# MDBU003_Schematic.net
KiCad netlist of a schematic drawn in Altium Designer
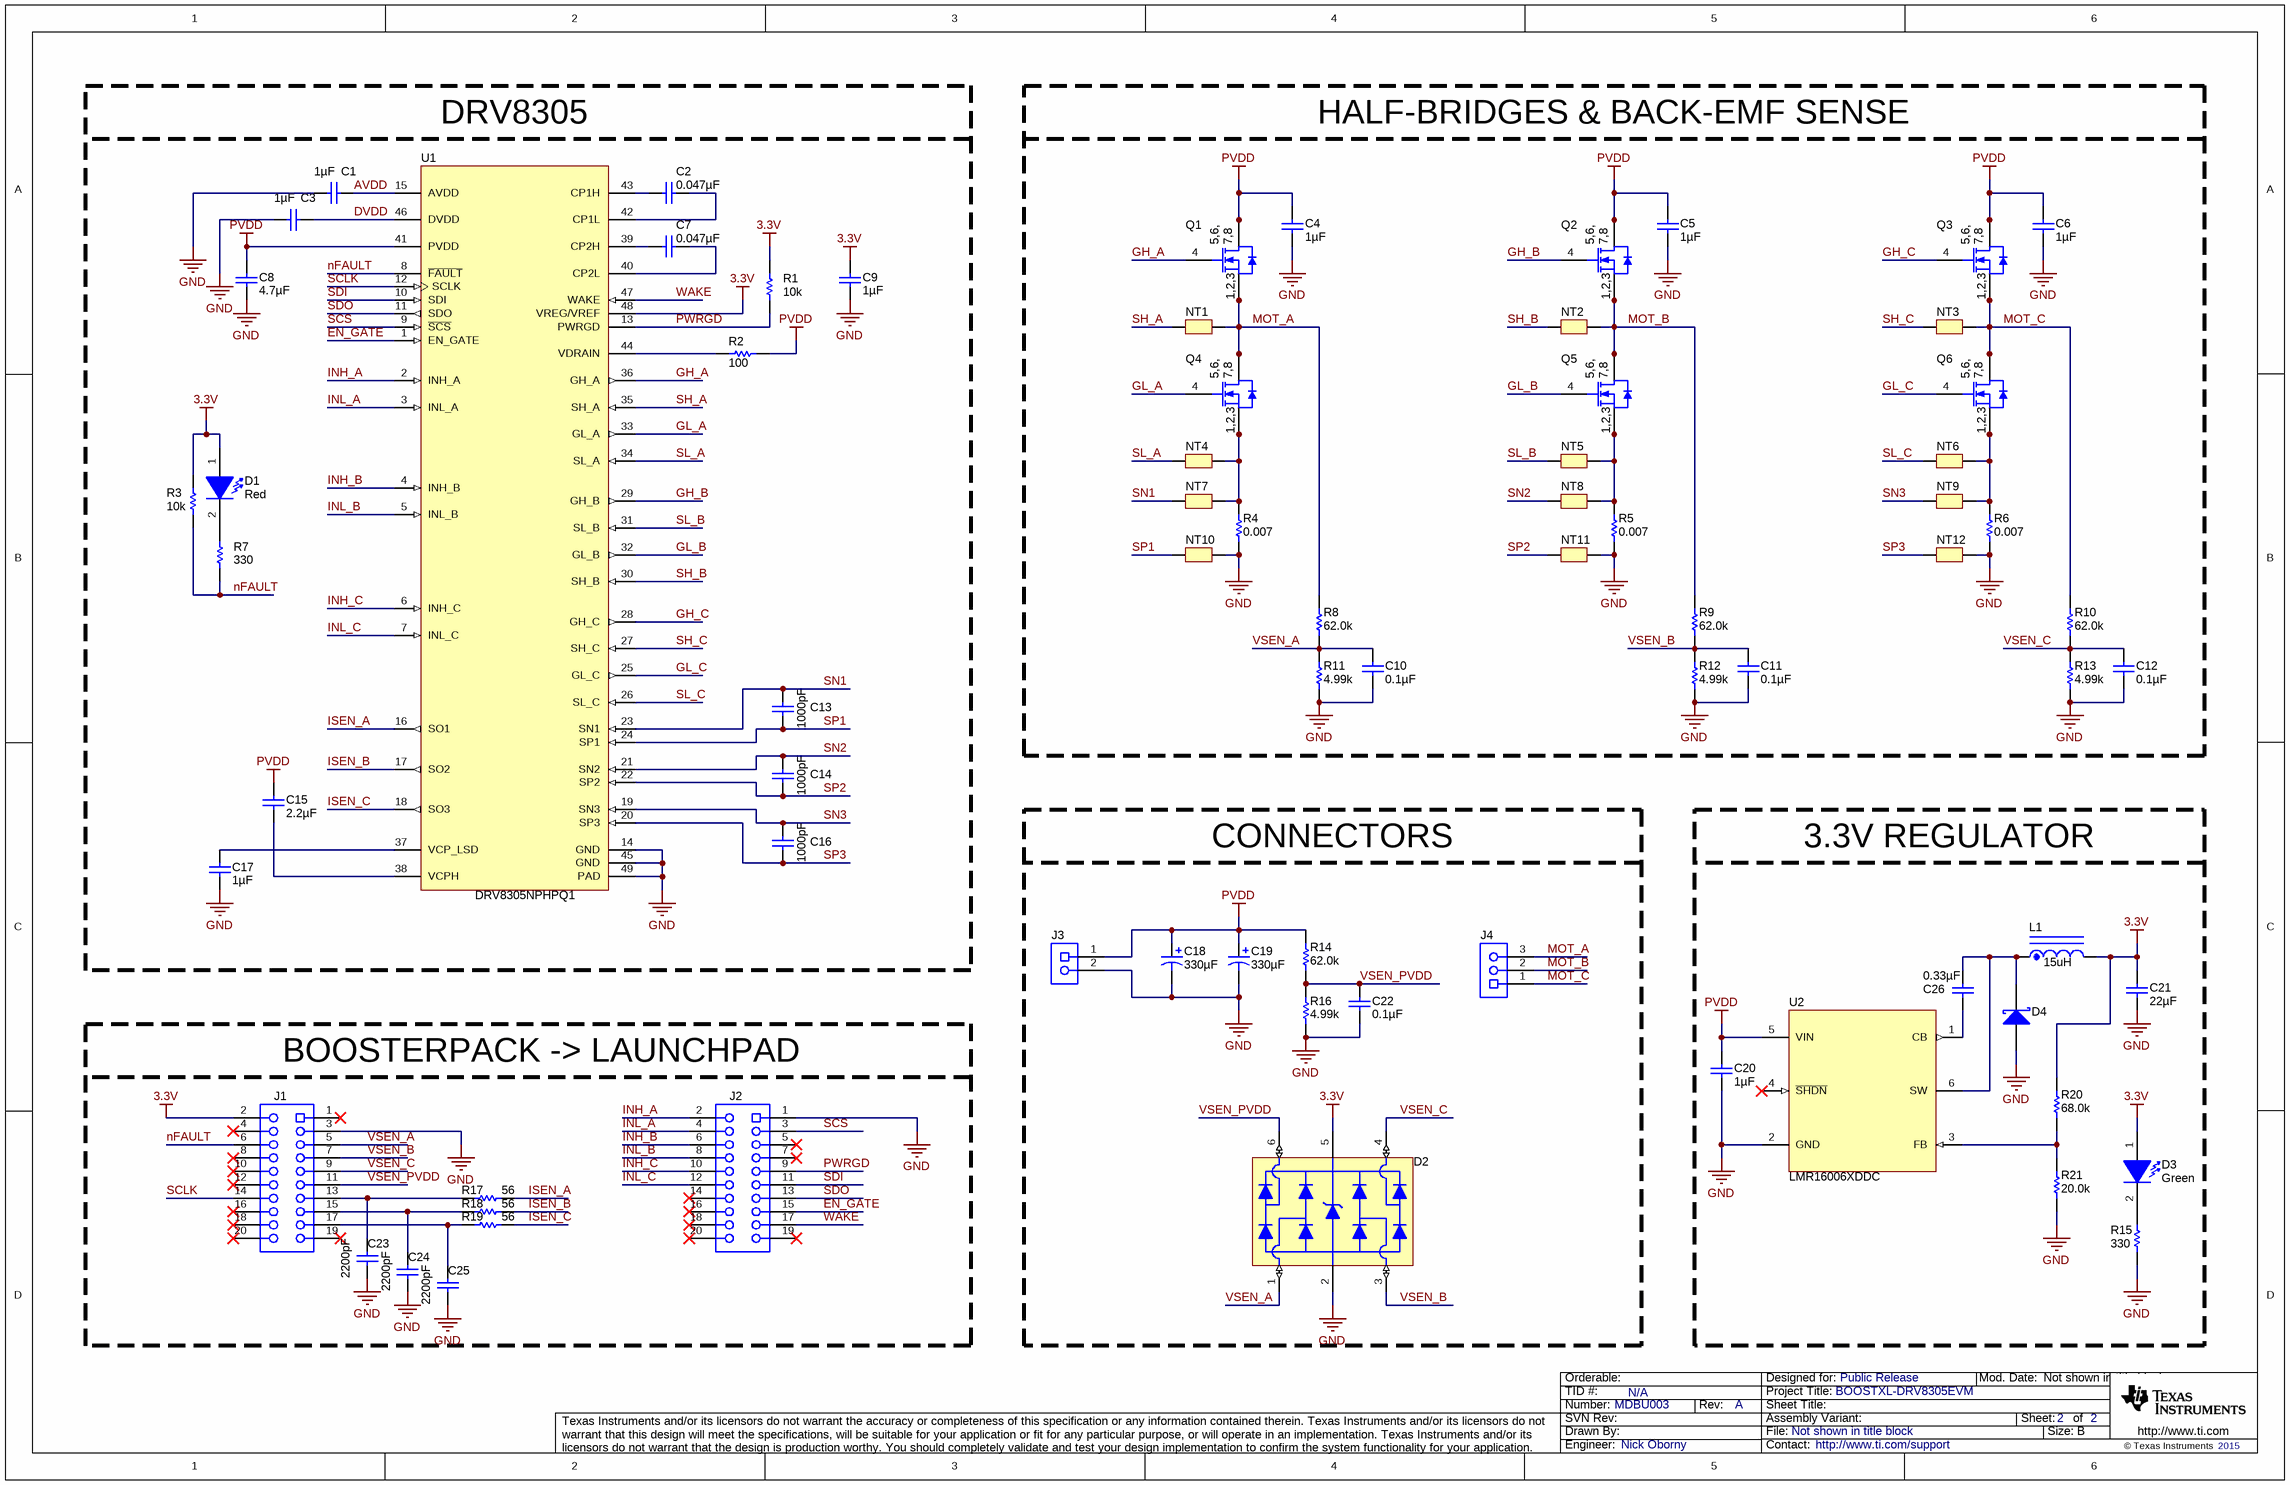
[diagram p0: MDBU003_Schematic.SchDoc]

(export (version "E")
  (design (tool "Eeschema 10.0.6"))
  (components
    (comp (ref "C1")
      (value "C1608X7R1C105K")
      (footprint "0603L")
      (description "CAP, CERM, 1 µF, 16 V, +/- 10%, X7R, 0603")
      (fields
        (field (name "VALUEDISPLAYED") "1µF")
        (field (name "MANUFACTURER") "TDK")
        (field (name "PUBLISHER") "Texas Instruments")
      )
      (libsource (lib "Capacitor_Ceramic") (part "C1608X7R1C105K"))
    )
    (comp (ref "C2")
      (value "C0603C473K1RACTU")
      (footprint "0603L")
      (description "CAP, CERM, 0.047uF, 100V, +/-10%, X7R, 0603")
      (fields
        (field (name "VALUEDISPLAYED") "0.047µF")
        (field (name "MANUFACTURER") "Kemet")
        (field (name "PUBLISHER") "Texas Instruments")
      )
      (libsource (lib "Capacitor_Ceramic") (part "GRM188R72A104KA35D"))
    )
    (comp (ref "C3")
      (value "C1608X7R1C105K")
      (footprint "0603L")
      (description "CAP, CERM, 1 µF, 16 V, +/- 10%, X7R, 0603")
      (fields
        (field (name "VALUEDISPLAYED") "1µF")
        (field (name "MANUFACTURER") "TDK")
        (field (name "PUBLISHER") "Texas Instruments")
      )
      (libsource (lib "Capacitor_Ceramic") (part "C1608X7R1C105K"))
    )
    (comp (ref "C4")
      (value "UMK107AB7105KA-T")
      (footprint "0603L")
      (description "CAP, CERM, 1 µF, 50 V, +/- 10%, X7R, 0603")
      (fields
        (field (name "VALUEDISPLAYED") "1µF")
        (field (name "MANUFACTURER") "Taiyo Yuden")
        (field (name "PUBLISHER") "Texas Instruments")
      )
      (libsource (lib "Capacitor_Ceramic") (part "UMK107AB7105KA-T"))
    )
    (comp (ref "C5")
      (value "UMK107AB7105KA-T")
      (footprint "0603L")
      (description "CAP, CERM, 1 µF, 50 V, +/- 10%, X7R, 0603")
      (fields
        (field (name "VALUEDISPLAYED") "1µF")
        (field (name "MANUFACTURER") "Taiyo Yuden")
        (field (name "PUBLISHER") "Texas Instruments")
      )
      (libsource (lib "Capacitor_Ceramic") (part "UMK107AB7105KA-T"))
    )
    (comp (ref "C6")
      (value "UMK107AB7105KA-T")
      (footprint "0603L")
      (description "CAP, CERM, 1 µF, 50 V, +/- 10%, X7R, 0603")
      (fields
        (field (name "VALUEDISPLAYED") "1µF")
        (field (name "MANUFACTURER") "Taiyo Yuden")
        (field (name "PUBLISHER") "Texas Instruments")
      )
      (libsource (lib "Capacitor_Ceramic") (part "UMK107AB7105KA-T"))
    )
    (comp (ref "C7")
      (value "C0603C473K1RACTU")
      (footprint "0603L")
      (description "CAP, CERM, 0.047uF, 100V, +/-10%, X7R, 0603")
      (fields
        (field (name "VALUEDISPLAYED") "0.047µF")
        (field (name "MANUFACTURER") "Kemet")
        (field (name "PUBLISHER") "Texas Instruments")
      )
      (libsource (lib "Capacitor_Ceramic") (part "GRM188R72A104KA35D"))
    )
    (comp (ref "C8")
      (value "GRM31CR71H475KA12L")
      (footprint "1206L")
      (description "CAP, CERM, 4.7 µF, 50 V, +/- 10%, X7R, 1206")
      (fields
        (field (name "VALUEDISPLAYED") "4.7µF")
        (field (name "MANUFACTURER") "MuRata")
        (field (name "PUBLISHER") "Texas Instruments")
      )
      (libsource (lib "Capacitor_Ceramic") (part "GRM31CR71H475KA12L"))
    )
    (comp (ref "C9")
      (value "C1608X7R1C105K")
      (footprint "0603L")
      (description "CAP, CERM, 1 µF, 16 V, +/- 10%, X7R, 0603")
      (fields
        (field (name "VALUEDISPLAYED") "1µF")
        (field (name "MANUFACTURER") "TDK")
        (field (name "PUBLISHER") "Texas Instruments")
      )
      (libsource (lib "Capacitor_Ceramic") (part "C1608X7R1C105K"))
    )
    (comp (ref "C10")
      (value "C0603C104J4RACTU")
      (footprint "0603L")
      (description "CAP, CERM, 0.1 µF, 16 V, +/- 5%, X7R, 0603")
      (fields
        (field (name "VALUEDISPLAYED") "0.1µF")
        (field (name "MANUFACTURER") "Kemet")
        (field (name "PUBLISHER") "Texas Instruments")
      )
      (libsource (lib "Capacitor_Ceramic") (part "C0603C104J4RACTU"))
    )
    (comp (ref "C11")
      (value "C0603C104J4RACTU")
      (footprint "0603L")
      (description "CAP, CERM, 0.1 µF, 16 V, +/- 5%, X7R, 0603")
      (fields
        (field (name "VALUEDISPLAYED") "0.1µF")
        (field (name "MANUFACTURER") "Kemet")
        (field (name "PUBLISHER") "Texas Instruments")
      )
      (libsource (lib "Capacitor_Ceramic") (part "C0603C104J4RACTU"))
    )
    (comp (ref "C12")
      (value "C0603C104J4RACTU")
      (footprint "0603L")
      (description "CAP, CERM, 0.1 µF, 16 V, +/- 5%, X7R, 0603")
      (fields
        (field (name "VALUEDISPLAYED") "0.1µF")
        (field (name "MANUFACTURER") "Kemet")
        (field (name "PUBLISHER") "Texas Instruments")
      )
      (libsource (lib "Capacitor_Ceramic") (part "C0603C104J4RACTU"))
    )
    (comp (ref "C13")
      (value "GRM188R71C102KA01D")
      (footprint "0603L")
      (description "CAP, CERM, 1000pF, 16V, +/-10%, X7R, 0603")
      (fields
        (field (name "VALUEDISPLAYED") "1000pF")
        (field (name "MANUFACTURER") "MuRata")
        (field (name "PUBLISHER") "Texas Instruments")
      )
      (libsource (lib "Capacitor_Ceramic") (part "GRM188R71C102KA01D"))
    )
    (comp (ref "C14")
      (value "GRM188R71C102KA01D")
      (footprint "0603L")
      (description "CAP, CERM, 1000pF, 16V, +/-10%, X7R, 0603")
      (fields
        (field (name "VALUEDISPLAYED") "1000pF")
        (field (name "MANUFACTURER") "MuRata")
        (field (name "PUBLISHER") "Texas Instruments")
      )
      (libsource (lib "Capacitor_Ceramic") (part "GRM188R71C102KA01D"))
    )
    (comp (ref "C15")
      (value "GRM32ER72A225KA35L")
      (footprint "1210L")
      (description "CAP, CERM, 2.2 µF, 100 V, +/- 10%, X7R, 1210")
      (fields
        (field (name "VALUEDISPLAYED") "2.2µF")
        (field (name "MANUFACTURER") "MuRata")
        (field (name "PUBLISHER") "Texas Instruments")
      )
      (libsource (lib "Capacitor_Ceramic") (part "GRM32ER72A225KA35L"))
    )
    (comp (ref "C16")
      (value "GRM188R71C102KA01D")
      (footprint "0603L")
      (description "CAP, CERM, 1000pF, 16V, +/-10%, X7R, 0603")
      (fields
        (field (name "VALUEDISPLAYED") "1000pF")
        (field (name "MANUFACTURER") "MuRata")
        (field (name "PUBLISHER") "Texas Instruments")
      )
      (libsource (lib "Capacitor_Ceramic") (part "GRM188R71C102KA01D"))
    )
    (comp (ref "C17")
      (value "C1608X7R1C105K")
      (footprint "0603L")
      (description "CAP, CERM, 1 µF, 16 V, +/- 10%, X7R, 0603")
      (fields
        (field (name "VALUEDISPLAYED") "1µF")
        (field (name "MANUFACTURER") "TDK")
        (field (name "PUBLISHER") "Texas Instruments")
      )
      (libsource (lib "Capacitor_Ceramic") (part "C1608X7R1C105K"))
    )
    (comp (ref "C18")
      (value "EEE-FT1H331AP")
      (footprint "SM_RADIAL_G")
      (description "CAP, AL, 330 µF, 50 V, +/- 20%, 0.3 ohm, SMD")
      (fields
        (field (name "VALUEDISPLAYED") "330µF")
        (field (name "MANUFACTURER") "Panasonic")
        (field (name "PUBLISHER") "Texas Instruments")
      )
      (libsource (lib "Capacitor_Aluminum") (part "EEE-FC1H221P"))
    )
    (comp (ref "C19")
      (value "EEE-FT1H331AP")
      (footprint "SM_RADIAL_G")
      (description "CAP, AL, 330 µF, 50 V, +/- 20%, 0.3 ohm, SMD")
      (fields
        (field (name "VALUEDISPLAYED") "330µF")
        (field (name "MANUFACTURER") "Panasonic")
        (field (name "PUBLISHER") "Texas Instruments")
      )
      (libsource (lib "Capacitor_Aluminum") (part "EEE-FC1H221P"))
    )
    (comp (ref "C20")
      (value "UMK107AB7105KA-T")
      (footprint "0603L")
      (description "CAP, CERM, 1 µF, 50 V, +/- 10%, X7R, 0603")
      (fields
        (field (name "VALUEDISPLAYED") "1µF")
        (field (name "MANUFACTURER") "Taiyo Yuden")
        (field (name "PUBLISHER") "Texas Instruments")
      )
      (libsource (lib "Capacitor_Ceramic") (part "UMK107AB7105KA-T"))
    )
    (comp (ref "C21")
      (value "GRM31CR71A226KE15L")
      (footprint "1206L")
      (description "CAP, CERM, 22 µF, 10 V, +/- 10%, X7R, 1206")
      (fields
        (field (name "VALUEDISPLAYED") "22µF")
        (field (name "MANUFACTURER") "MuRata")
        (field (name "PUBLISHER") "Texas Instruments")
      )
      (libsource (lib "Capacitor_Ceramic") (part "GRM31CR71A226KE15L"))
    )
    (comp (ref "C22")
      (value "C0603C104J4RACTU")
      (footprint "0603L")
      (description "CAP, CERM, 0.1 µF, 16 V, +/- 5%, X7R, 0603")
      (fields
        (field (name "VALUEDISPLAYED") "0.1µF")
        (field (name "MANUFACTURER") "Kemet")
        (field (name "PUBLISHER") "Texas Instruments")
      )
      (libsource (lib "Capacitor_Ceramic") (part "C0603C104J4RACTU"))
    )
    (comp (ref "C23")
      (value "GRM188R71C222KA01D")
      (footprint "0603L")
      (description "CAP, CERM, 2200pF, 16V, +/-10%, X7R, 0603")
      (fields
        (field (name "VALUEDISPLAYED") "2200pF")
        (field (name "MANUFACTURER") "MuRata")
        (field (name "PUBLISHER") "Texas Instruments")
      )
      (libsource (lib "Capacitor_Ceramic") (part "GRM188R71C222KA01D"))
    )
    (comp (ref "C24")
      (value "GRM188R71C222KA01D")
      (footprint "0603L")
      (description "CAP, CERM, 2200pF, 16V, +/-10%, X7R, 0603")
      (fields
        (field (name "VALUEDISPLAYED") "2200pF")
        (field (name "MANUFACTURER") "MuRata")
        (field (name "PUBLISHER") "Texas Instruments")
      )
      (libsource (lib "Capacitor_Ceramic") (part "GRM188R71C222KA01D"))
    )
    (comp (ref "C25")
      (value "GRM188R71C222KA01D")
      (footprint "0603L")
      (description "CAP, CERM, 2200pF, 16V, +/-10%, X7R, 0603")
      (fields
        (field (name "VALUEDISPLAYED") "2200pF")
        (field (name "MANUFACTURER") "MuRata")
        (field (name "PUBLISHER") "Texas Instruments")
      )
      (libsource (lib "Capacitor_Ceramic") (part "GRM188R71C222KA01D"))
    )
    (comp (ref "C26")
      (value "GRM188R71C334KA01D")
      (footprint "0603L")
      (description "CAP, CERM, 0.33 µF, 16 V, +/- 10%, X7R, 0603")
      (fields
        (field (name "VALUEDISPLAYED") "0.33µF")
        (field (name "MANUFACTURER") "MuRata")
        (field (name "PUBLISHER") "Texas Instruments")
      )
      (libsource (lib "Capacitor_Ceramic") (part "GRM188R71C334KA01D"))
    )
    (comp (ref "D1")
      (value "Red")
      (footprint "LED_LTST-C170")
      (description "LED, Red, SMD")
      (fields
        (field (name "MANUFACTURER") "Lite-On")
        (field (name "PARTNUMBER") "LTST-C170KRKT")
        (field (name "PUBLISHER") "Texas Instruments")
      )
      (libsource (lib "LED") (part "LTST-C170KRKT"))
    )
    (comp (ref "D2")
      (value "NUP4201MR6T1G")
      (footprint "TSOP-6")
      (description "Transient Voltage Suppressors, 5 V, TSOP-6")
      (fields
        (field (name "MANUFACTURER") "ON Semiconductor")
        (field (name "SYMBOLCREATOR") "Altium")
        (field (name "PUBLISHER") "Texas Instruments")
      )
      (libsource (lib "Other_Passive") (part "NUP4201MR6T1G"))
    )
    (comp (ref "D3")
      (value "Green")
      (footprint "LED_LTST-C171")
      (description "LED, Green, SMD")
      (fields
        (field (name "MANUFACTURER") "Lite-On")
        (field (name "PARTNUMBER") "LTST-C171GKT")
        (field (name "PUBLISHER") "Texas Instruments")
      )
      (libsource (lib "LED") (part "LTST-C171GKT"))
    )
    (comp (ref "D4")
      (value "MBR1H100SFT3G")
      (footprint "SOD-123FL")
      (description "Diode, Schottky, 100 V, 1 A, SOD-123FL")
      (fields (field (name "MANUFACTURER") "ON Semiconductor") (field (name "PUBLISHER") "Texas Instruments"))
      (libsource (lib "Diode") (part "MBR1H100SFT3G"))
    )
    (comp (ref "J1")
      (value "CRD-081413-A-G")
      (footprint "Major_CRD-081413-A-x")
      (description "Receptacle, 2.54 mm, 10x2, Gold, TH")
      (fields
        (field (name "MANUFACTURER") "Major League Electronics")
        (field (name "SYMBOLCREATOR") "a0412235")
        (field (name "PUBLISHER") "Texas Instruments")
      )
      (libsource (lib "Connectors_Other") (part "CRD-081413-A-G"))
    )
    (comp (ref "J2")
      (value "CRD-081413-A-G")
      (footprint "Major_CRD-081413-A-x")
      (description "Receptacle, 2.54 mm, 10x2, Gold, TH")
      (fields
        (field (name "MANUFACTURER") "Major League Electronics")
        (field (name "SYMBOLCREATOR") "a0412235")
        (field (name "PUBLISHER") "Texas Instruments")
      )
      (libsource (lib "Connectors_Other") (part "CRD-081413-A-G"))
    )
    (comp (ref "J3")
      (value "691 101 710 002")
      (footprint "Wurth_691101710002")
      (description "Terminal Block, 5 mm, 2x1, Tin, TH")
      (fields
        (field (name "MANUFACTURER") "Wurth Elektronik eiSos")
        (field (name "SYMBOLCREATOR") "a0412235")
        (field (name "PUBLISHER") "Texas Instruments")
      )
      (libsource (lib "Connectors_Other") (part "691 101 710 002"))
    )
    (comp (ref "J4")
      (value "691 101 710 003")
      (footprint "Wurth_691101710003")
      (description "Terminal Block, 5 mm, 3x1, Tin, TH")
      (fields
        (field (name "MANUFACTURER") "Wurth Elektronik eiSos")
        (field (name "SYMBOLCREATOR") "a0412235")
        (field (name "PUBLISHER") "Texas Instruments")
      )
      (libsource (lib "Connectors_Other") (part "691 101 710 003"))
    )
    (comp (ref "L1")
      (value "15uH")
      (footprint "SD53")
      (description "Inductor, Shielded Drum Core, Ferrite, 15 µH, 1.1 A, 0.122 ohm, SMD")
      (fields
        (field (name "PARTNUMBER") "SD53-150-R")
        (field (name "MANUFACTURER") "Cooper Bussman")
        (field (name "SYMBOLCREATOR") "a0412235")
        (field (name "PUBLISHER") "Texas Instruments")
      )
      (libsource (lib "Inductor_Other") (part "SD53-150-R"))
    )
    (comp (ref "NT1")
      (value "Net-Tie")
      (footprint "Net-Tie_10mil")
      (description "Single point connection between nets.")
      (fields (field (name "SYMBOLCREATOR") "codlsc") (field (name "PUBLISHER") "Texas Instruments"))
      (libsource (lib "MiscParts") (part "Net-Tie"))
    )
    (comp (ref "NT2")
      (value "Net-Tie")
      (footprint "Net-Tie_10mil")
      (description "Single point connection between nets.")
      (fields (field (name "SYMBOLCREATOR") "codlsc") (field (name "PUBLISHER") "Texas Instruments"))
      (libsource (lib "MiscParts") (part "Net-Tie"))
    )
    (comp (ref "NT3")
      (value "Net-Tie")
      (footprint "Net-Tie_10mil")
      (description "Single point connection between nets.")
      (fields (field (name "SYMBOLCREATOR") "codlsc") (field (name "PUBLISHER") "Texas Instruments"))
      (libsource (lib "MiscParts") (part "Net-Tie"))
    )
    (comp (ref "NT4")
      (value "Net-Tie")
      (footprint "Net-Tie_10mil")
      (description "Single point connection between nets.")
      (fields (field (name "SYMBOLCREATOR") "codlsc") (field (name "PUBLISHER") "Texas Instruments"))
      (libsource (lib "MiscParts") (part "Net-Tie"))
    )
    (comp (ref "NT5")
      (value "Net-Tie")
      (footprint "Net-Tie_10mil")
      (description "Single point connection between nets.")
      (fields (field (name "SYMBOLCREATOR") "codlsc") (field (name "PUBLISHER") "Texas Instruments"))
      (libsource (lib "MiscParts") (part "Net-Tie"))
    )
    (comp (ref "NT6")
      (value "Net-Tie")
      (footprint "Net-Tie_10mil")
      (description "Single point connection between nets.")
      (fields (field (name "SYMBOLCREATOR") "codlsc") (field (name "PUBLISHER") "Texas Instruments"))
      (libsource (lib "MiscParts") (part "Net-Tie"))
    )
    (comp (ref "NT7")
      (value "Net-Tie")
      (footprint "Net-Tie_10mil")
      (description "Single point connection between nets.")
      (fields (field (name "SYMBOLCREATOR") "codlsc") (field (name "PUBLISHER") "Texas Instruments"))
      (libsource (lib "MiscParts") (part "Net-Tie"))
    )
    (comp (ref "NT8")
      (value "Net-Tie")
      (footprint "Net-Tie_10mil")
      (description "Single point connection between nets.")
      (fields (field (name "SYMBOLCREATOR") "codlsc") (field (name "PUBLISHER") "Texas Instruments"))
      (libsource (lib "MiscParts") (part "Net-Tie"))
    )
    (comp (ref "NT9")
      (value "Net-Tie")
      (footprint "Net-Tie_10mil")
      (description "Single point connection between nets.")
      (fields (field (name "SYMBOLCREATOR") "codlsc") (field (name "PUBLISHER") "Texas Instruments"))
      (libsource (lib "MiscParts") (part "Net-Tie"))
    )
    (comp (ref "NT10")
      (value "Net-Tie")
      (footprint "Net-Tie_10mil")
      (description "Single point connection between nets.")
      (fields (field (name "SYMBOLCREATOR") "codlsc") (field (name "PUBLISHER") "Texas Instruments"))
      (libsource (lib "MiscParts") (part "Net-Tie"))
    )
    (comp (ref "NT11")
      (value "Net-Tie")
      (footprint "Net-Tie_10mil")
      (description "Single point connection between nets.")
      (fields (field (name "SYMBOLCREATOR") "codlsc") (field (name "PUBLISHER") "Texas Instruments"))
      (libsource (lib "MiscParts") (part "Net-Tie"))
    )
    (comp (ref "NT12")
      (value "Net-Tie")
      (footprint "Net-Tie_10mil")
      (description "Single point connection between nets.")
      (fields (field (name "SYMBOLCREATOR") "codlsc") (field (name "PUBLISHER") "Texas Instruments"))
      (libsource (lib "MiscParts") (part "Net-Tie"))
    )
    (comp (ref "Q1")
      (value "CSD18540Q5B")
      (footprint "TRANS_NexFET_Q5B")
      (description "MOSFET, N-CH, 60 V, 28 A, SON 5x6mm")
      (fields
        (field (name "MANUFACTURER") "Texas Instruments")
        (field (name "PUBLISHER") "Texas Instruments")
      )
      (libsource (lib "FETs") (part "CSD18540Q5B"))
    )
    (comp (ref "Q2")
      (value "CSD18540Q5B")
      (footprint "TRANS_NexFET_Q5B")
      (description "MOSFET, N-CH, 60 V, 28 A, SON 5x6mm")
      (fields
        (field (name "MANUFACTURER") "Texas Instruments")
        (field (name "PUBLISHER") "Texas Instruments")
      )
      (libsource (lib "FETs") (part "CSD18540Q5B"))
    )
    (comp (ref "Q3")
      (value "CSD18540Q5B")
      (footprint "TRANS_NexFET_Q5B")
      (description "MOSFET, N-CH, 60 V, 28 A, SON 5x6mm")
      (fields
        (field (name "MANUFACTURER") "Texas Instruments")
        (field (name "PUBLISHER") "Texas Instruments")
      )
      (libsource (lib "FETs") (part "CSD18540Q5B"))
    )
    (comp (ref "Q4")
      (value "CSD18540Q5B")
      (footprint "TRANS_NexFET_Q5B")
      (description "MOSFET, N-CH, 60 V, 28 A, SON 5x6mm")
      (fields
        (field (name "MANUFACTURER") "Texas Instruments")
        (field (name "PUBLISHER") "Texas Instruments")
      )
      (libsource (lib "FETs") (part "CSD18540Q5B"))
    )
    (comp (ref "Q5")
      (value "CSD18540Q5B")
      (footprint "TRANS_NexFET_Q5B")
      (description "MOSFET, N-CH, 60 V, 28 A, SON 5x6mm")
      (fields
        (field (name "MANUFACTURER") "Texas Instruments")
        (field (name "PUBLISHER") "Texas Instruments")
      )
      (libsource (lib "FETs") (part "CSD18540Q5B"))
    )
    (comp (ref "Q6")
      (value "CSD18540Q5B")
      (footprint "TRANS_NexFET_Q5B")
      (description "MOSFET, N-CH, 60 V, 28 A, SON 5x6mm")
      (fields
        (field (name "MANUFACTURER") "Texas Instruments")
        (field (name "PUBLISHER") "Texas Instruments")
      )
      (libsource (lib "FETs") (part "CSD18540Q5B"))
    )
    (comp (ref "R1")
      (value "10k")
      (footprint "0603L")
      (description "RES, 10k ohm, 5%, 0.1W, 0603")
      (fields
        (field (name "PARTNUMBER") "CRCW060310K0JNEA")
        (field (name "MANUFACTURER") "Vishay-Dale")
        (field (name "PUBLISHER") "Texas Instruments")
      )
      (libsource (lib "Resistor_0603") (part "CRCW060310K0JNEA"))
    )
    (comp (ref "R2")
      (value "100")
      (footprint "0603L")
      (description "RES, 100 ohm, 5%, 0.1W, 0603")
      (fields
        (field (name "PARTNUMBER") "CRCW0603100RJNEA")
        (field (name "MANUFACTURER") "Vishay-Dale")
        (field (name "PUBLISHER") "Texas Instruments")
      )
      (libsource (lib "Resistor_0603") (part "CRCW0603100RJNEA"))
    )
    (comp (ref "R3")
      (value "10k")
      (footprint "0603L")
      (description "RES, 10k ohm, 5%, 0.1W, 0603")
      (fields
        (field (name "PARTNUMBER") "CRCW060310K0JNEA")
        (field (name "MANUFACTURER") "Vishay-Dale")
        (field (name "PUBLISHER") "Texas Instruments")
      )
      (libsource (lib "Resistor_0603") (part "CRCW060310K0JNEA"))
    )
    (comp (ref "R4")
      (value "CRE2512-FZ-R007E-3")
      (footprint "2512L")
      (description "RES SMD 0.007 OHM 1% 3W 2512")
      (fields
        (field (name "VALUEDISPLAYED") "0.007")
        (field (name "MANUFACTURER") "Bourns Inc.")
        (field (name "PUBLISHER") "Texas Instruments")
      )
      (libsource (lib "Resistor_2512") (part "PMR100HZPFU7L00"))
    )
    (comp (ref "R5")
      (value "CRE2512-FZ-R007E-3")
      (footprint "2512L")
      (description "RES SMD 0.007 OHM 1% 3W 2512")
      (fields
        (field (name "VALUEDISPLAYED") "0.007")
        (field (name "MANUFACTURER") "Bourns Inc.")
        (field (name "PUBLISHER") "Texas Instruments")
      )
      (libsource (lib "Resistor_2512") (part "PMR100HZPFU7L00"))
    )
    (comp (ref "R6")
      (value "CRE2512-FZ-R007E-3")
      (footprint "2512L")
      (description "RES SMD 0.007 OHM 1% 3W 2512")
      (fields
        (field (name "VALUEDISPLAYED") "0.007")
        (field (name "MANUFACTURER") "Bourns Inc.")
        (field (name "PUBLISHER") "Texas Instruments")
      )
      (libsource (lib "Resistor_2512") (part "PMR100HZPFU7L00"))
    )
    (comp (ref "R7")
      (value "330")
      (footprint "0603L")
      (description "RES, 330 ohm, 5%, 0.1W, 0603")
      (fields
        (field (name "PARTNUMBER") "CRCW0603330RJNEA")
        (field (name "MANUFACTURER") "Vishay-Dale")
        (field (name "PUBLISHER") "Texas Instruments")
      )
      (libsource (lib "Resistor_0603") (part "CRCW0603330RJNEA"))
    )
    (comp (ref "R8")
      (value "RC0603FR-0762KL")
      (footprint "0603L")
      (description "RES, 62.0 k, 1%, 0.1 W, 0603")
      (fields
        (field (name "VALUEDISPLAYED") "62.0k")
        (field (name "MANUFACTURER") "Yageo America")
        (field (name "PUBLISHER") "Texas Instruments")
      )
      (libsource (lib "Resistor_0603") (part "RC0603FR-0762KL"))
    )
    (comp (ref "R9")
      (value "RC0603FR-0762KL")
      (footprint "0603L")
      (description "RES, 62.0 k, 1%, 0.1 W, 0603")
      (fields
        (field (name "VALUEDISPLAYED") "62.0k")
        (field (name "MANUFACTURER") "Yageo America")
        (field (name "PUBLISHER") "Texas Instruments")
      )
      (libsource (lib "Resistor_0603") (part "RC0603FR-0762KL"))
    )
    (comp (ref "R10")
      (value "RC0603FR-0762KL")
      (footprint "0603L")
      (description "RES, 62.0 k, 1%, 0.1 W, 0603")
      (fields
        (field (name "VALUEDISPLAYED") "62.0k")
        (field (name "MANUFACTURER") "Yageo America")
        (field (name "PUBLISHER") "Texas Instruments")
      )
      (libsource (lib "Resistor_0603") (part "RC0603FR-0762KL"))
    )
    (comp (ref "R11")
      (value "RC0603FR-074K99L")
      (footprint "0603L")
      (description "RES, 4.99 k, 1%, 0.1 W, 0603")
      (fields
        (field (name "VALUEDISPLAYED") "4.99k")
        (field (name "MANUFACTURER") "Yageo America")
        (field (name "PUBLISHER") "Texas Instruments")
      )
      (libsource (lib "Resistor_0603") (part "RC0603FR-074K99L"))
    )
    (comp (ref "R12")
      (value "RC0603FR-074K99L")
      (footprint "0603L")
      (description "RES, 4.99 k, 1%, 0.1 W, 0603")
      (fields
        (field (name "VALUEDISPLAYED") "4.99k")
        (field (name "MANUFACTURER") "Yageo America")
        (field (name "PUBLISHER") "Texas Instruments")
      )
      (libsource (lib "Resistor_0603") (part "RC0603FR-074K99L"))
    )
    (comp (ref "R13")
      (value "RC0603FR-074K99L")
      (footprint "0603L")
      (description "RES, 4.99 k, 1%, 0.1 W, 0603")
      (fields
        (field (name "VALUEDISPLAYED") "4.99k")
        (field (name "MANUFACTURER") "Yageo America")
        (field (name "PUBLISHER") "Texas Instruments")
      )
      (libsource (lib "Resistor_0603") (part "RC0603FR-074K99L"))
    )
    (comp (ref "R14")
      (value "RC0603FR-0762KL")
      (footprint "0603L")
      (description "RES, 62.0 k, 1%, 0.1 W, 0603")
      (fields
        (field (name "VALUEDISPLAYED") "62.0k")
        (field (name "MANUFACTURER") "Yageo America")
        (field (name "PUBLISHER") "Texas Instruments")
      )
      (libsource (lib "Resistor_0603") (part "RC0603FR-0762KL"))
    )
    (comp (ref "R15")
      (value "330")
      (footprint "0603L")
      (description "RES, 330 ohm, 5%, 0.1W, 0603")
      (fields
        (field (name "PARTNUMBER") "CRCW0603330RJNEA")
        (field (name "MANUFACTURER") "Vishay-Dale")
        (field (name "PUBLISHER") "Texas Instruments")
      )
      (libsource (lib "Resistor_0603") (part "CRCW0603330RJNEA"))
    )
    (comp (ref "R16")
      (value "RC0603FR-074K99L")
      (footprint "0603L")
      (description "RES, 4.99 k, 1%, 0.1 W, 0603")
      (fields
        (field (name "VALUEDISPLAYED") "4.99k")
        (field (name "MANUFACTURER") "Yageo America")
        (field (name "PUBLISHER") "Texas Instruments")
      )
      (libsource (lib "Resistor_0603") (part "RC0603FR-074K99L"))
    )
    (comp (ref "R17")
      (value "56")
      (footprint "0603L")
      (description "RES, 56 ohm, 5%, 0.1W, 0603")
      (fields
        (field (name "PARTNUMBER") "CRCW060356R0JNEA")
        (field (name "MANUFACTURER") "Vishay-Dale")
        (field (name "PUBLISHER") "Texas Instruments")
      )
      (libsource (lib "Resistor_0603") (part "CRCW060356R0JNEA"))
    )
    (comp (ref "R18")
      (value "56")
      (footprint "0603L")
      (description "RES, 56 ohm, 5%, 0.1W, 0603")
      (fields
        (field (name "PARTNUMBER") "CRCW060356R0JNEA")
        (field (name "MANUFACTURER") "Vishay-Dale")
        (field (name "PUBLISHER") "Texas Instruments")
      )
      (libsource (lib "Resistor_0603") (part "CRCW060356R0JNEA"))
    )
    (comp (ref "R19")
      (value "56")
      (footprint "0603L")
      (description "RES, 56 ohm, 5%, 0.1W, 0603")
      (fields
        (field (name "PARTNUMBER") "CRCW060356R0JNEA")
        (field (name "MANUFACTURER") "Vishay-Dale")
        (field (name "PUBLISHER") "Texas Instruments")
      )
      (libsource (lib "Resistor_0603") (part "CRCW060356R0JNEA"))
    )
    (comp (ref "R20")
      (value "RC0603FR-0768KL")
      (footprint "0603L")
      (description "RES, 68.0 k, 1%, 0.1 W, 0603")
      (fields
        (field (name "VALUEDISPLAYED") "68.0k")
        (field (name "MANUFACTURER") "Yageo America")
        (field (name "PUBLISHER") "Texas Instruments")
      )
      (libsource (lib "Resistor_0603") (part "RC0603FR-0768KL"))
    )
    (comp (ref "R21")
      (value "CRCW060320K0FKEA")
      (footprint "0603L")
      (description "RES, 20.0 k, 1%, 0.1 W, 0603")
      (fields
        (field (name "VALUEDISPLAYED") "20.0k")
        (field (name "MANUFACTURER") "Vishay-Dale")
        (field (name "PUBLISHER") "Texas Instruments")
      )
      (libsource (lib "Resistor_0603") (part "CRCW060320K0FKEA"))
    )
    (comp (ref "U1")
      (value "DRV8305NPHPQ1")
      (footprint "PHP0048G_L")
      (fields
        (field (name "ALTERNATE PARTNUMBER") "DRV83053EPHPQ1")
        (field (name "MANUFACTURER") "Texas Instruments")
        (field (name "SYMBOLCREATOR") "Altium")
        (field (name "PUBLISHER") "Texas Instruments")
      )
      (libsource (lib "TI_Pre_RTM") (part "DRV83053EPHPRQ1"))
    )
    (comp (ref "U2")
      (value "LMR16006XDDC")
      (footprint "DDC0006A_N")
      (description "Wide Input Voltage Range Buck Regulator with High Efficiency Sleep Mode, DDC0006A")
      (fields
        (field (name "MANUFACTURER") "Texas Instruments")
        (field (name "SYMBOLCREATOR") "x0208326")
        (field (name "PUBLISHER") "Texas Instruments")
      )
      (libsource (lib "TI_Pre_RTM") (part "LMR16006XDDC"))
    )
  )
  (nets
    (net (code "1") (name "/AVDD") (class "Default")
      (node (ref "C1") (pin "2") (pinfunction "2_2") (pintype "passive"))
      (node (ref "U1") (pin "15") (pinfunction "AVDD_15") (pintype "power_in"))
    )
    (net (code "2") (name "/DVDD") (class "Default")
      (node (ref "C3") (pin "2") (pinfunction "2_2") (pintype "passive"))
      (node (ref "U1") (pin "46") (pinfunction "DVDD_46") (pintype "power_in"))
    )
    (net (code "3") (name "/EN_GATE") (class "Default")
      (node (ref "J2") (pin "15") (pinfunction "15_15") (pintype "passive"))
      (node (ref "U1") (pin "1") (pinfunction "EN_GATE_1") (pintype "input"))
    )
    (net (code "4") (name "/GH_A") (class "Default")
      (node (ref "Q1") (pin "4") (pinfunction "G_4") (pintype "passive"))
      (node (ref "U1") (pin "36") (pinfunction "GH_A_36") (pintype "output"))
    )
    (net (code "5") (name "/GH_B") (class "Default")
      (node (ref "Q2") (pin "4") (pinfunction "G_4") (pintype "passive"))
      (node (ref "U1") (pin "29") (pinfunction "GH_B_29") (pintype "output"))
    )
    (net (code "6") (name "/GH_C") (class "Default")
      (node (ref "Q3") (pin "4") (pinfunction "G_4") (pintype "passive"))
      (node (ref "U1") (pin "28") (pinfunction "GH_C_28") (pintype "output"))
    )
    (net (code "7") (name "/GL_A") (class "Default")
      (node (ref "Q4") (pin "4") (pinfunction "G_4") (pintype "passive"))
      (node (ref "U1") (pin "33") (pinfunction "GL_A_33") (pintype "output"))
    )
    (net (code "8") (name "/GL_B") (class "Default")
      (node (ref "Q5") (pin "4") (pinfunction "G_4") (pintype "passive"))
      (node (ref "U1") (pin "32") (pinfunction "GL_B_32") (pintype "output"))
    )
    (net (code "9") (name "/GL_C") (class "Default")
      (node (ref "Q6") (pin "4") (pinfunction "G_4") (pintype "passive"))
      (node (ref "U1") (pin "25") (pinfunction "GL_C_25") (pintype "output"))
    )
    (net (code "10") (name "/INH_A") (class "Default")
      (node (ref "J2") (pin "2") (pinfunction "2_2") (pintype "passive"))
      (node (ref "U1") (pin "2") (pinfunction "INH_A_2") (pintype "input"))
    )
    (net (code "11") (name "/INH_B") (class "Default")
      (node (ref "J2") (pin "6") (pinfunction "6_6") (pintype "passive"))
      (node (ref "U1") (pin "4") (pinfunction "INH_B_4") (pintype "input"))
    )
    (net (code "12") (name "/INH_C") (class "Default")
      (node (ref "J2") (pin "10") (pinfunction "10_10") (pintype "passive"))
      (node (ref "U1") (pin "6") (pinfunction "INH_C_6") (pintype "input"))
    )
    (net (code "13") (name "/INL_A") (class "Default")
      (node (ref "J2") (pin "4") (pinfunction "4_4") (pintype "passive"))
      (node (ref "U1") (pin "3") (pinfunction "INL_A_3") (pintype "input"))
    )
    (net (code "14") (name "/INL_B") (class "Default")
      (node (ref "J2") (pin "8") (pinfunction "8_8") (pintype "passive"))
      (node (ref "U1") (pin "5") (pinfunction "INL_B_5") (pintype "input"))
    )
    (net (code "15") (name "/INL_C") (class "Default")
      (node (ref "J2") (pin "12") (pinfunction "12_12") (pintype "passive"))
      (node (ref "U1") (pin "7") (pinfunction "INL_C_7") (pintype "input"))
    )
    (net (code "16") (name "/ISEN_A") (class "Default")
      (node (ref "R17") (pin "2") (pinfunction "2_2") (pintype "passive"))
      (node (ref "U1") (pin "16") (pinfunction "SO1_16") (pintype "output"))
    )
    (net (code "17") (name "/ISEN_B") (class "Default")
      (node (ref "R18") (pin "2") (pinfunction "2_2") (pintype "passive"))
      (node (ref "U1") (pin "17") (pinfunction "SO2_17") (pintype "output"))
    )
    (net (code "18") (name "/ISEN_C") (class "Default")
      (node (ref "R19") (pin "2") (pinfunction "2_2") (pintype "passive"))
      (node (ref "U1") (pin "18") (pinfunction "SO3_18") (pintype "output"))
    )
    (net (code "19") (name "/MOT_A") (class "Default")
      (node (ref "J4") (pin "3") (pinfunction "3_3") (pintype "passive"))
      (node (ref "NT1") (pin "2") (pinfunction "2_2") (pintype "passive"))
      (node (ref "Q1") (pin "1") (pinfunction "S_1") (pintype "passive"))
      (node (ref "Q1") (pin "2") (pinfunction "S_2") (pintype "passive"))
      (node (ref "Q1") (pin "3") (pinfunction "S_3") (pintype "passive"))
      (node (ref "Q4") (pin "5") (pinfunction "D_5") (pintype "passive"))
      (node (ref "Q4") (pin "6") (pinfunction "D_6") (pintype "passive"))
      (node (ref "Q4") (pin "7") (pinfunction "D_7") (pintype "passive"))
      (node (ref "Q4") (pin "8") (pinfunction "D_8") (pintype "passive"))
      (node (ref "R8") (pin "2") (pinfunction "2_2") (pintype "passive"))
    )
    (net (code "20") (name "/MOT_B") (class "Default")
      (node (ref "J4") (pin "2") (pinfunction "2_2") (pintype "passive"))
      (node (ref "NT2") (pin "2") (pinfunction "2_2") (pintype "passive"))
      (node (ref "Q2") (pin "1") (pinfunction "S_1") (pintype "passive"))
      (node (ref "Q2") (pin "2") (pinfunction "S_2") (pintype "passive"))
      (node (ref "Q2") (pin "3") (pinfunction "S_3") (pintype "passive"))
      (node (ref "Q5") (pin "5") (pinfunction "D_5") (pintype "passive"))
      (node (ref "Q5") (pin "6") (pinfunction "D_6") (pintype "passive"))
      (node (ref "Q5") (pin "7") (pinfunction "D_7") (pintype "passive"))
      (node (ref "Q5") (pin "8") (pinfunction "D_8") (pintype "passive"))
      (node (ref "R9") (pin "2") (pinfunction "2_2") (pintype "passive"))
    )
    (net (code "21") (name "/MOT_C") (class "Default")
      (node (ref "J4") (pin "1") (pinfunction "1_1") (pintype "passive"))
      (node (ref "NT3") (pin "2") (pinfunction "2_2") (pintype "passive"))
      (node (ref "Q3") (pin "1") (pinfunction "S_1") (pintype "passive"))
      (node (ref "Q3") (pin "2") (pinfunction "S_2") (pintype "passive"))
      (node (ref "Q3") (pin "3") (pinfunction "S_3") (pintype "passive"))
      (node (ref "Q6") (pin "5") (pinfunction "D_5") (pintype "passive"))
      (node (ref "Q6") (pin "6") (pinfunction "D_6") (pintype "passive"))
      (node (ref "Q6") (pin "7") (pinfunction "D_7") (pintype "passive"))
      (node (ref "Q6") (pin "8") (pinfunction "D_8") (pintype "passive"))
      (node (ref "R10") (pin "2") (pinfunction "2_2") (pintype "passive"))
    )
    (net (code "22") (name "/PWRGD") (class "Default")
      (node (ref "J2") (pin "9") (pinfunction "9_9") (pintype "passive"))
      (node (ref "R1") (pin "1") (pinfunction "1_1") (pintype "passive"))
      (node (ref "U1") (pin "13") (pinfunction "PWRGD_13") (pintype "open_collector"))
    )
    (net (code "23") (name "/SCLK") (class "Default")
      (node (ref "J1") (pin "14") (pinfunction "14_14") (pintype "passive"))
      (node (ref "U1") (pin "12") (pinfunction "SCLK_12") (pintype "input"))
    )
    (net (code "24") (name "/SCS") (class "Default")
      (node (ref "J2") (pin "3") (pinfunction "3_3") (pintype "passive"))
      (node (ref "U1") (pin "9") (pinfunction "SCS_9") (pintype "input"))
    )
    (net (code "25") (name "/SDI") (class "Default")
      (node (ref "J2") (pin "11") (pinfunction "11_11") (pintype "passive"))
      (node (ref "U1") (pin "10") (pinfunction "SDI_10") (pintype "input"))
    )
    (net (code "26") (name "/SDO") (class "Default")
      (node (ref "J2") (pin "13") (pinfunction "13_13") (pintype "passive"))
      (node (ref "U1") (pin "11") (pinfunction "SDO_11") (pintype "output"))
    )
    (net (code "27") (name "/SH_A") (class "Default")
      (node (ref "NT1") (pin "1") (pinfunction "1_1") (pintype "passive"))
      (node (ref "U1") (pin "35") (pinfunction "SH_A_35") (pintype "input"))
    )
    (net (code "28") (name "/SH_B") (class "Default")
      (node (ref "NT2") (pin "1") (pinfunction "1_1") (pintype "passive"))
      (node (ref "U1") (pin "30") (pinfunction "SH_B_30") (pintype "input"))
    )
    (net (code "29") (name "/SH_C") (class "Default")
      (node (ref "NT3") (pin "1") (pinfunction "1_1") (pintype "passive"))
      (node (ref "U1") (pin "27") (pinfunction "SH_C_27") (pintype "input"))
    )
    (net (code "30") (name "/SL_A") (class "Default")
      (node (ref "NT4") (pin "1") (pinfunction "1_1") (pintype "passive"))
      (node (ref "U1") (pin "34") (pinfunction "SL_A_34") (pintype "input"))
    )
    (net (code "31") (name "/SL_B") (class "Default")
      (node (ref "NT5") (pin "1") (pinfunction "1_1") (pintype "passive"))
      (node (ref "U1") (pin "31") (pinfunction "SL_B_31") (pintype "input"))
    )
    (net (code "32") (name "/SL_C") (class "Default")
      (node (ref "NT6") (pin "1") (pinfunction "1_1") (pintype "passive"))
      (node (ref "U1") (pin "26") (pinfunction "SL_C_26") (pintype "input"))
    )
    (net (code "33") (name "/SN1") (class "Default")
      (node (ref "C13") (pin "1") (pinfunction "1_1") (pintype "passive"))
      (node (ref "NT7") (pin "1") (pinfunction "1_1") (pintype "passive"))
      (node (ref "U1") (pin "23") (pinfunction "SN1_23") (pintype "input"))
    )
    (net (code "34") (name "/SN2") (class "Default")
      (node (ref "C14") (pin "1") (pinfunction "1_1") (pintype "passive"))
      (node (ref "NT8") (pin "1") (pinfunction "1_1") (pintype "passive"))
      (node (ref "U1") (pin "21") (pinfunction "SN2_21") (pintype "input"))
    )
    (net (code "35") (name "/SN3") (class "Default")
      (node (ref "C16") (pin "1") (pinfunction "1_1") (pintype "passive"))
      (node (ref "NT9") (pin "1") (pinfunction "1_1") (pintype "passive"))
      (node (ref "U1") (pin "19") (pinfunction "SN3_19") (pintype "input"))
    )
    (net (code "36") (name "/SP1") (class "Default")
      (node (ref "C13") (pin "2") (pinfunction "2_2") (pintype "passive"))
      (node (ref "NT10") (pin "1") (pinfunction "1_1") (pintype "passive"))
      (node (ref "U1") (pin "24") (pinfunction "SP1_24") (pintype "input"))
    )
    (net (code "37") (name "/SP2") (class "Default")
      (node (ref "C14") (pin "2") (pinfunction "2_2") (pintype "passive"))
      (node (ref "NT11") (pin "1") (pinfunction "1_1") (pintype "passive"))
      (node (ref "U1") (pin "22") (pinfunction "SP2_22") (pintype "input"))
    )
    (net (code "38") (name "/SP3") (class "Default")
      (node (ref "C16") (pin "2") (pinfunction "2_2") (pintype "passive"))
      (node (ref "NT12") (pin "1") (pinfunction "1_1") (pintype "passive"))
      (node (ref "U1") (pin "20") (pinfunction "SP3_20") (pintype "input"))
    )
    (net (code "39") (name "/VSEN_A") (class "Default")
      (node (ref "C10") (pin "1") (pinfunction "1_1") (pintype "passive"))
      (node (ref "D2") (pin "1") (pinfunction "I/O_1") (pintype "bidirectional"))
      (node (ref "J1") (pin "5") (pinfunction "5_5") (pintype "passive"))
      (node (ref "R11") (pin "2") (pinfunction "2_2") (pintype "passive"))
      (node (ref "R8") (pin "1") (pinfunction "1_1") (pintype "passive"))
    )
    (net (code "40") (name "/VSEN_B") (class "Default")
      (node (ref "C11") (pin "1") (pinfunction "1_1") (pintype "passive"))
      (node (ref "D2") (pin "3") (pinfunction "I/O_3") (pintype "bidirectional"))
      (node (ref "J1") (pin "7") (pinfunction "7_7") (pintype "passive"))
      (node (ref "R12") (pin "2") (pinfunction "2_2") (pintype "passive"))
      (node (ref "R9") (pin "1") (pinfunction "1_1") (pintype "passive"))
    )
    (net (code "41") (name "/VSEN_C") (class "Default")
      (node (ref "C12") (pin "1") (pinfunction "1_1") (pintype "passive"))
      (node (ref "D2") (pin "4") (pinfunction "I/O_4") (pintype "bidirectional"))
      (node (ref "J1") (pin "9") (pinfunction "9_9") (pintype "passive"))
      (node (ref "R10") (pin "1") (pinfunction "1_1") (pintype "passive"))
      (node (ref "R13") (pin "2") (pinfunction "2_2") (pintype "passive"))
    )
    (net (code "42") (name "/VSEN_PVDD") (class "Default")
      (node (ref "C22") (pin "1") (pinfunction "1_1") (pintype "passive"))
      (node (ref "D2") (pin "6") (pinfunction "I/O_6") (pintype "bidirectional"))
      (node (ref "J1") (pin "11") (pinfunction "11_11") (pintype "passive"))
      (node (ref "R14") (pin "1") (pinfunction "1_1") (pintype "passive"))
      (node (ref "R16") (pin "2") (pinfunction "2_2") (pintype "passive"))
    )
    (net (code "43") (name "/WAKE") (class "Default")
      (node (ref "J2") (pin "17") (pinfunction "17_17") (pintype "passive"))
      (node (ref "U1") (pin "47") (pinfunction "WAKE_47") (pintype "input"))
    )
    (net (code "44") (name "/nFAULT") (class "Default")
      (node (ref "J1") (pin "6") (pinfunction "6_6") (pintype "passive"))
      (node (ref "R3") (pin "1") (pinfunction "1_1") (pintype "passive"))
      (node (ref "R7") (pin "1") (pinfunction "1_1") (pintype "passive"))
      (node (ref "U1") (pin "8") (pinfunction "FAULT_8") (pintype "open_collector"))
    )
    (net (code "45") (name "3.3V") (class "Default")
      (node (ref "C21") (pin "1") (pinfunction "1_1") (pintype "passive"))
      (node (ref "C9") (pin "2") (pinfunction "2_2") (pintype "passive"))
      (node (ref "D1") (pin "1") (pinfunction "A_1") (pintype "passive"))
      (node (ref "D2") (pin "5") (pinfunction "VP_5") (pintype "power_in"))
      (node (ref "D3") (pin "1") (pinfunction "A_1") (pintype "passive"))
      (node (ref "J1") (pin "2") (pinfunction "2_2") (pintype "passive"))
      (node (ref "L1") (pin "2") (pinfunction "2_2") (pintype "passive"))
      (node (ref "R1") (pin "2") (pinfunction "2_2") (pintype "passive"))
      (node (ref "R20") (pin "2") (pinfunction "2_2") (pintype "passive"))
      (node (ref "R3") (pin "2") (pinfunction "2_2") (pintype "passive"))
      (node (ref "U1") (pin "48") (pinfunction "VREG/VREF_48") (pintype "power_in"))
    )
    (net (code "46") (name "GND") (class "Default")
      (node (ref "C1") (pin "1") (pinfunction "1_1") (pintype "passive"))
      (node (ref "C10") (pin "2") (pinfunction "2_2") (pintype "passive"))
      (node (ref "C11") (pin "2") (pinfunction "2_2") (pintype "passive"))
      (node (ref "C12") (pin "2") (pinfunction "2_2") (pintype "passive"))
      (node (ref "C17") (pin "2") (pinfunction "2_2") (pintype "passive"))
      (node (ref "C18") (pin "2") (pinfunction "-_2") (pintype "passive"))
      (node (ref "C19") (pin "2") (pinfunction "-_2") (pintype "passive"))
      (node (ref "C20") (pin "2") (pinfunction "2_2") (pintype "passive"))
      (node (ref "C21") (pin "2") (pinfunction "2_2") (pintype "passive"))
      (node (ref "C22") (pin "2") (pinfunction "2_2") (pintype "passive"))
      (node (ref "C23") (pin "2") (pinfunction "2_2") (pintype "passive"))
      (node (ref "C24") (pin "2") (pinfunction "2_2") (pintype "passive"))
      (node (ref "C25") (pin "2") (pinfunction "2_2") (pintype "passive"))
      (node (ref "C3") (pin "1") (pinfunction "1_1") (pintype "passive"))
      (node (ref "C4") (pin "2") (pinfunction "2_2") (pintype "passive"))
      (node (ref "C5") (pin "2") (pinfunction "2_2") (pintype "passive"))
      (node (ref "C6") (pin "2") (pinfunction "2_2") (pintype "passive"))
      (node (ref "C8") (pin "1") (pinfunction "1_1") (pintype "passive"))
      (node (ref "C9") (pin "1") (pinfunction "1_1") (pintype "passive"))
      (node (ref "D2") (pin "2") (pinfunction "VN_2") (pintype "power_in"))
      (node (ref "D4") (pin "2") (pinfunction "A_2") (pintype "passive"))
      (node (ref "J1") (pin "3") (pinfunction "3_3") (pintype "passive"))
      (node (ref "J2") (pin "1") (pinfunction "1_1") (pintype "passive"))
      (node (ref "J3") (pin "2") (pinfunction "2_2") (pintype "passive"))
      (node (ref "NT10") (pin "2") (pinfunction "2_2") (pintype "passive"))
      (node (ref "NT11") (pin "2") (pinfunction "2_2") (pintype "passive"))
      (node (ref "NT12") (pin "2") (pinfunction "2_2") (pintype "passive"))
      (node (ref "R11") (pin "1") (pinfunction "1_1") (pintype "passive"))
      (node (ref "R12") (pin "1") (pinfunction "1_1") (pintype "passive"))
      (node (ref "R13") (pin "1") (pinfunction "1_1") (pintype "passive"))
      (node (ref "R15") (pin "1") (pinfunction "1_1") (pintype "passive"))
      (node (ref "R16") (pin "1") (pinfunction "1_1") (pintype "passive"))
      (node (ref "R21") (pin "1") (pinfunction "1_1") (pintype "passive"))
      (node (ref "R4") (pin "1") (pinfunction "1_1") (pintype "passive"))
      (node (ref "R5") (pin "1") (pinfunction "1_1") (pintype "passive"))
      (node (ref "R6") (pin "1") (pinfunction "1_1") (pintype "passive"))
      (node (ref "U1") (pin "14") (pinfunction "GND_14") (pintype "power_in"))
      (node (ref "U1") (pin "45") (pinfunction "GND_45") (pintype "power_in"))
      (node (ref "U1") (pin "49") (pinfunction "PAD_49") (pintype "power_in"))
      (node (ref "U2") (pin "2") (pinfunction "GND_2") (pintype "power_in"))
    )
    (net (code "47") (name "Net-(C23-Pad1)") (class "Default")
      (node (ref "C23") (pin "1") (pinfunction "1_1") (pintype "passive"))
      (node (ref "J1") (pin "13") (pinfunction "13_13") (pintype "passive"))
      (node (ref "R17") (pin "1") (pinfunction "1_1") (pintype "passive"))
    )
    (net (code "48") (name "Net-(C24-Pad1)") (class "Default")
      (node (ref "C24") (pin "1") (pinfunction "1_1") (pintype "passive"))
      (node (ref "J1") (pin "15") (pinfunction "15_15") (pintype "passive"))
      (node (ref "R18") (pin "1") (pinfunction "1_1") (pintype "passive"))
    )
    (net (code "49") (name "Net-(C25-Pad1)") (class "Default")
      (node (ref "C25") (pin "1") (pinfunction "1_1") (pintype "passive"))
      (node (ref "J1") (pin "17") (pinfunction "17_17") (pintype "passive"))
      (node (ref "R19") (pin "1") (pinfunction "1_1") (pintype "passive"))
    )
    (net (code "50") (name "Net-(D1-K)") (class "Default")
      (node (ref "D1") (pin "2") (pinfunction "K_2") (pintype "passive"))
      (node (ref "R7") (pin "2") (pinfunction "2_2") (pintype "passive"))
    )
    (net (code "51") (name "Net-(D3-K)") (class "Default")
      (node (ref "D3") (pin "2") (pinfunction "K_2") (pintype "passive"))
      (node (ref "R15") (pin "2") (pinfunction "2_2") (pintype "passive"))
    )
    (net (code "52") (name "Net-(D4-K)") (class "Default")
      (node (ref "C26") (pin "1") (pinfunction "1_1") (pintype "passive"))
      (node (ref "D4") (pin "1") (pinfunction "K_1") (pintype "passive"))
      (node (ref "L1") (pin "1") (pinfunction "1_1") (pintype "passive"))
      (node (ref "U2") (pin "6") (pinfunction "SW_6") (pintype "power_in"))
    )
    (net (code "53") (name "Net-(NT4-Pad2)") (class "Default")
      (node (ref "NT4") (pin "2") (pinfunction "2_2") (pintype "passive"))
      (node (ref "NT7") (pin "2") (pinfunction "2_2") (pintype "passive"))
      (node (ref "Q4") (pin "1") (pinfunction "S_1") (pintype "passive"))
      (node (ref "Q4") (pin "2") (pinfunction "S_2") (pintype "passive"))
      (node (ref "Q4") (pin "3") (pinfunction "S_3") (pintype "passive"))
      (node (ref "R4") (pin "2") (pinfunction "2_2") (pintype "passive"))
    )
    (net (code "54") (name "Net-(NT5-Pad2)") (class "Default")
      (node (ref "NT5") (pin "2") (pinfunction "2_2") (pintype "passive"))
      (node (ref "NT8") (pin "2") (pinfunction "2_2") (pintype "passive"))
      (node (ref "Q5") (pin "1") (pinfunction "S_1") (pintype "passive"))
      (node (ref "Q5") (pin "2") (pinfunction "S_2") (pintype "passive"))
      (node (ref "Q5") (pin "3") (pinfunction "S_3") (pintype "passive"))
      (node (ref "R5") (pin "2") (pinfunction "2_2") (pintype "passive"))
    )
    (net (code "55") (name "Net-(NT6-Pad2)") (class "Default")
      (node (ref "NT6") (pin "2") (pinfunction "2_2") (pintype "passive"))
      (node (ref "NT9") (pin "2") (pinfunction "2_2") (pintype "passive"))
      (node (ref "Q6") (pin "1") (pinfunction "S_1") (pintype "passive"))
      (node (ref "Q6") (pin "2") (pinfunction "S_2") (pintype "passive"))
      (node (ref "Q6") (pin "3") (pinfunction "S_3") (pintype "passive"))
      (node (ref "R6") (pin "2") (pinfunction "2_2") (pintype "passive"))
    )
    (net (code "56") (name "Net-(U1-CP1H)") (class "Default")
      (node (ref "C2") (pin "1") (pinfunction "1_1") (pintype "passive"))
      (node (ref "U1") (pin "43") (pinfunction "CP1H_43") (pintype "passive"))
    )
    (net (code "57") (name "Net-(U1-CP1L)") (class "Default")
      (node (ref "C2") (pin "2") (pinfunction "2_2") (pintype "passive"))
      (node (ref "U1") (pin "42") (pinfunction "CP1L_42") (pintype "passive"))
    )
    (net (code "58") (name "Net-(U1-CP2H)") (class "Default")
      (node (ref "C7") (pin "1") (pinfunction "1_1") (pintype "passive"))
      (node (ref "U1") (pin "39") (pinfunction "CP2H_39") (pintype "passive"))
    )
    (net (code "59") (name "Net-(U1-CP2L)") (class "Default")
      (node (ref "C7") (pin "2") (pinfunction "2_2") (pintype "passive"))
      (node (ref "U1") (pin "40") (pinfunction "CP2L_40") (pintype "passive"))
    )
    (net (code "60") (name "Net-(U1-VCPH)") (class "Default")
      (node (ref "C15") (pin "2") (pinfunction "2_2") (pintype "passive"))
      (node (ref "U1") (pin "38") (pinfunction "VCPH_38") (pintype "passive"))
    )
    (net (code "61") (name "Net-(U1-VCP_LSD)") (class "Default")
      (node (ref "C17") (pin "1") (pinfunction "1_1") (pintype "passive"))
      (node (ref "U1") (pin "37") (pinfunction "VCP_LSD_37") (pintype "passive"))
    )
    (net (code "62") (name "Net-(U1-VDRAIN)") (class "Default")
      (node (ref "R2") (pin "1") (pinfunction "1_1") (pintype "passive"))
      (node (ref "U1") (pin "44") (pinfunction "VDRAIN_44") (pintype "power_in"))
    )
    (net (code "63") (name "Net-(U2-CB)") (class "Default")
      (node (ref "C26") (pin "2") (pinfunction "2_2") (pintype "passive"))
      (node (ref "U2") (pin "1") (pinfunction "CB_1") (pintype "output"))
    )
    (net (code "64") (name "Net-(U2-FB)") (class "Default")
      (node (ref "R20") (pin "1") (pinfunction "1_1") (pintype "passive"))
      (node (ref "R21") (pin "2") (pinfunction "2_2") (pintype "passive"))
      (node (ref "U2") (pin "3") (pinfunction "FB_3") (pintype "input"))
    )
    (net (code "65") (name "PVDD") (class "Default")
      (node (ref "C15") (pin "1") (pinfunction "1_1") (pintype "passive"))
      (node (ref "C18") (pin "1") (pinfunction "+_1") (pintype "passive"))
      (node (ref "C19") (pin "1") (pinfunction "+_1") (pintype "passive"))
      (node (ref "C20") (pin "1") (pinfunction "1_1") (pintype "passive"))
      (node (ref "C4") (pin "1") (pinfunction "1_1") (pintype "passive"))
      (node (ref "C5") (pin "1") (pinfunction "1_1") (pintype "passive"))
      (node (ref "C6") (pin "1") (pinfunction "1_1") (pintype "passive"))
      (node (ref "C8") (pin "2") (pinfunction "2_2") (pintype "passive"))
      (node (ref "J3") (pin "1") (pinfunction "1_1") (pintype "passive"))
      (node (ref "Q1") (pin "5") (pinfunction "D_5") (pintype "passive"))
      (node (ref "Q1") (pin "6") (pinfunction "D_6") (pintype "passive"))
      (node (ref "Q1") (pin "7") (pinfunction "D_7") (pintype "passive"))
      (node (ref "Q1") (pin "8") (pinfunction "D_8") (pintype "passive"))
      (node (ref "Q2") (pin "5") (pinfunction "D_5") (pintype "passive"))
      (node (ref "Q2") (pin "6") (pinfunction "D_6") (pintype "passive"))
      (node (ref "Q2") (pin "7") (pinfunction "D_7") (pintype "passive"))
      (node (ref "Q2") (pin "8") (pinfunction "D_8") (pintype "passive"))
      (node (ref "Q3") (pin "5") (pinfunction "D_5") (pintype "passive"))
      (node (ref "Q3") (pin "6") (pinfunction "D_6") (pintype "passive"))
      (node (ref "Q3") (pin "7") (pinfunction "D_7") (pintype "passive"))
      (node (ref "Q3") (pin "8") (pinfunction "D_8") (pintype "passive"))
      (node (ref "R14") (pin "2") (pinfunction "2_2") (pintype "passive"))
      (node (ref "R2") (pin "2") (pinfunction "2_2") (pintype "passive"))
      (node (ref "U1") (pin "41") (pinfunction "PVDD_41") (pintype "power_in"))
      (node (ref "U2") (pin "5") (pinfunction "VIN_5") (pintype "power_in"))
    )
    (net (code "66") (name "unconnected-(J1-Pad1)") (class "Default")
      (node (ref "J1") (pin "1") (pinfunction "1_1") (pintype "passive+no_connect"))
    )
    (net (code "67") (name "unconnected-(J1-Pad4)") (class "Default")
      (node (ref "J1") (pin "4") (pinfunction "4_4") (pintype "passive+no_connect"))
    )
    (net (code "68") (name "unconnected-(J1-Pad8)") (class "Default")
      (node (ref "J1") (pin "8") (pinfunction "8_8") (pintype "passive+no_connect"))
    )
    (net (code "69") (name "unconnected-(J1-Pad10)") (class "Default")
      (node (ref "J1") (pin "10") (pinfunction "10_10") (pintype "passive+no_connect"))
    )
    (net (code "70") (name "unconnected-(J1-Pad12)") (class "Default")
      (node (ref "J1") (pin "12") (pinfunction "12_12") (pintype "passive+no_connect"))
    )
    (net (code "71") (name "unconnected-(J1-Pad16)") (class "Default")
      (node (ref "J1") (pin "16") (pinfunction "16_16") (pintype "passive+no_connect"))
    )
    (net (code "72") (name "unconnected-(J1-Pad18)") (class "Default")
      (node (ref "J1") (pin "18") (pinfunction "18_18") (pintype "passive+no_connect"))
    )
    (net (code "73") (name "unconnected-(J1-Pad19)") (class "Default")
      (node (ref "J1") (pin "19") (pinfunction "19_19") (pintype "passive+no_connect"))
    )
    (net (code "74") (name "unconnected-(J1-Pad20)") (class "Default")
      (node (ref "J1") (pin "20") (pinfunction "20_20") (pintype "passive+no_connect"))
    )
    (net (code "75") (name "unconnected-(J2-Pad5)") (class "Default")
      (node (ref "J2") (pin "5") (pinfunction "5_5") (pintype "passive+no_connect"))
    )
    (net (code "76") (name "unconnected-(J2-Pad7)") (class "Default")
      (node (ref "J2") (pin "7") (pinfunction "7_7") (pintype "passive+no_connect"))
    )
    (net (code "77") (name "unconnected-(J2-Pad14)") (class "Default")
      (node (ref "J2") (pin "14") (pinfunction "14_14") (pintype "passive+no_connect"))
    )
    (net (code "78") (name "unconnected-(J2-Pad16)") (class "Default")
      (node (ref "J2") (pin "16") (pinfunction "16_16") (pintype "passive+no_connect"))
    )
    (net (code "79") (name "unconnected-(J2-Pad18)") (class "Default")
      (node (ref "J2") (pin "18") (pinfunction "18_18") (pintype "passive+no_connect"))
    )
    (net (code "80") (name "unconnected-(J2-Pad19)") (class "Default")
      (node (ref "J2") (pin "19") (pinfunction "19_19") (pintype "passive+no_connect"))
    )
    (net (code "81") (name "unconnected-(J2-Pad20)") (class "Default")
      (node (ref "J2") (pin "20") (pinfunction "20_20") (pintype "passive+no_connect"))
    )
    (net (code "82") (name "unconnected-(U2-SHDN-Pad4)") (class "Default")
      (node (ref "U2") (pin "4") (pinfunction "SHDN_4") (pintype "input+no_connect"))
    )
  )
)
